# SCH.net
KiCad netlist of a schematic drawn in Altium Designer
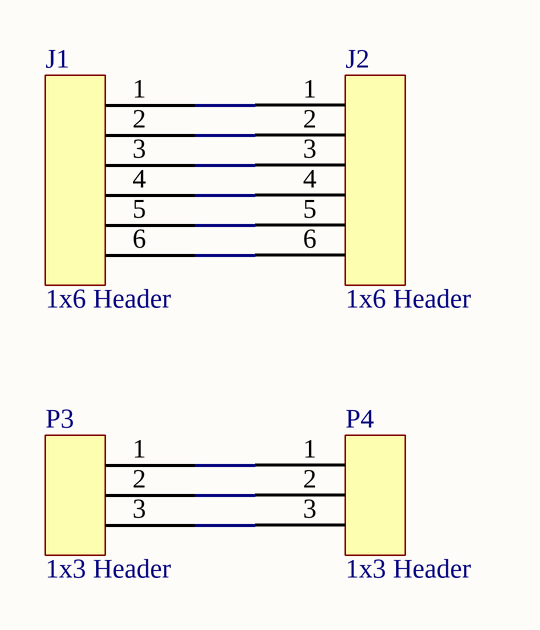
[diagram p0: SCH.SchDoc]

(export (version "E")
  (design (tool "Eeschema 10.0.6"))
  (components
    (comp (ref "J1")
      (value "1x6 Header")
      (footprint "1x6 Header 1.27")
      (libsource (lib "Schematic_Components") (part "1x6 Header"))
    )
    (comp (ref "J2")
      (value "1x6 Header")
      (footprint "1x6 Header 1.27")
      (libsource (lib "") (part "1x6 Header_1"))
    )
    (comp (ref "P3")
      (value "1x3 Header")
      (footprint "1x3 Header 1.27")
      (libsource (lib "") (part "1x3 Header_1"))
    )
    (comp (ref "P4")
      (value "1x3 Header")
      (footprint "1x3 Header 1.27")
      (libsource (lib "Schematic_Components") (part "1x3 Header"))
    )
  )
  (nets
    (net (code "1") (name "Net-(J1-Pad1)") (class "Default")
      (node (ref "J1") (pin "1") (pintype "passive"))
      (node (ref "J2") (pin "1") (pintype "passive"))
    )
    (net (code "2") (name "Net-(J1-Pad2)") (class "Default")
      (node (ref "J1") (pin "2") (pintype "passive"))
      (node (ref "J2") (pin "2") (pintype "passive"))
    )
    (net (code "3") (name "Net-(J1-Pad3)") (class "Default")
      (node (ref "J1") (pin "3") (pintype "passive"))
      (node (ref "J2") (pin "3") (pintype "passive"))
    )
    (net (code "4") (name "Net-(J1-Pad4)") (class "Default")
      (node (ref "J1") (pin "4") (pintype "passive"))
      (node (ref "J2") (pin "4") (pintype "passive"))
    )
    (net (code "5") (name "Net-(J1-Pad5)") (class "Default")
      (node (ref "J1") (pin "5") (pintype "passive"))
      (node (ref "J2") (pin "5") (pintype "passive"))
    )
    (net (code "6") (name "Net-(J1-Pad6)") (class "Default")
      (node (ref "J1") (pin "6") (pintype "passive"))
      (node (ref "J2") (pin "6") (pintype "passive"))
    )
    (net (code "7") (name "Net-(P3-Pad1)") (class "Default")
      (node (ref "P3") (pin "1") (pintype "passive"))
      (node (ref "P4") (pin "1") (pintype "passive"))
    )
    (net (code "8") (name "Net-(P3-Pad2)") (class "Default")
      (node (ref "P3") (pin "2") (pintype "passive"))
      (node (ref "P4") (pin "2") (pintype "passive"))
    )
    (net (code "9") (name "Net-(P3-Pad3)") (class "Default")
      (node (ref "P3") (pin "3") (pintype "passive"))
      (node (ref "P4") (pin "3") (pintype "passive"))
    )
  )
)
